# Color_music_board_with_mic.net
KiCad netlist of a schematic drawn in EAGLE
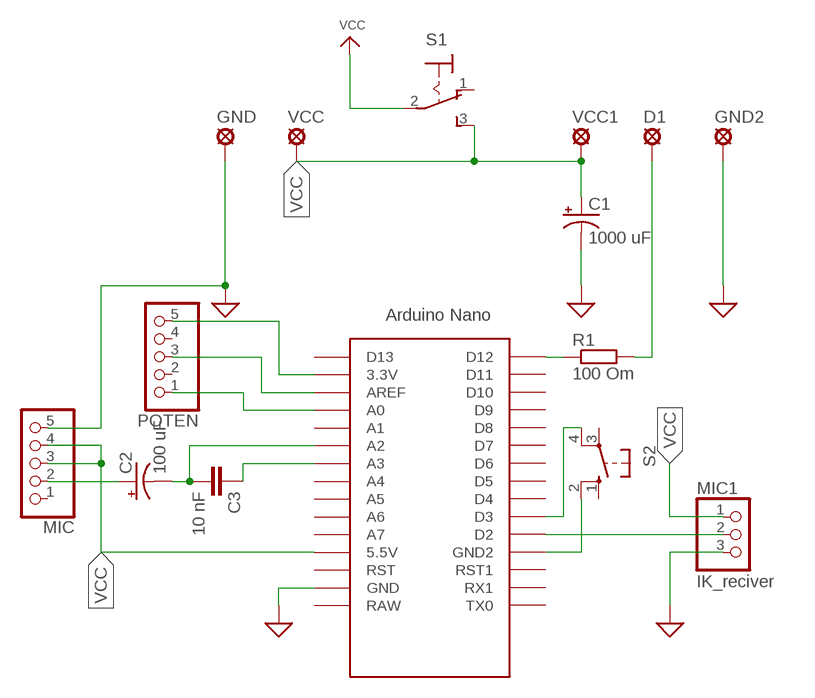
[diagram p0: schematic, sheet 1]

(export (version "E")
  (design (tool "Eeschema 10.0.6"))
  (components
    (comp (ref "C1")
      (value "1000 uF")
      (footprint "eagle-import:TT5D10")
      (libsource (lib "eagle-import") (part "CPOL-USTT5D10"))
    )
    (comp (ref "C2")
      (value "100 uF")
      (footprint "eagle-import:E2,5-6")
      (libsource (lib "eagle-import") (part "CPOL-USE2.5-6"))
    )
    (comp (ref "C3")
      (value "10 nF")
      (footprint "eagle-import:C2.5-2")
      (libsource (lib "eagle-import") (part "C2.5/2"))
    )
    (comp (ref "D1")
      (value "SE14")
      (footprint "eagle-import:SE14")
      (libsource (lib "eagle-import") (part "SE14"))
    )
    (comp (ref "GND")
      (value "SE14")
      (footprint "eagle-import:SE14")
      (libsource (lib "eagle-import") (part "SE14"))
    )
    (comp (ref "GND2")
      (value "SE14")
      (footprint "eagle-import:SE14")
      (libsource (lib "eagle-import") (part "SE14"))
    )
    (comp (ref "MIC")
      (value "PINHD-1X5")
      (footprint "eagle-import:1X05")
      (libsource (lib "eagle-import") (part "PINHD-1X5"))
    )
    (comp (ref "MIC1")
      (value "IK_reciver")
      (footprint "eagle-import:1X03")
      (libsource (lib "eagle-import") (part "PINHD-1X3"))
    )
    (comp (ref "POTEN")
      (value "PINHD-1X5")
      (footprint "eagle-import:1X05")
      (libsource (lib "eagle-import") (part "PINHD-1X5"))
    )
    (comp (ref "R1")
      (value "100 Om")
      (footprint "eagle-import:0207_7")
      (libsource (lib "eagle-import") (part "R-EU_0207/7"))
    )
    (comp (ref "S1")
      (value "320-916")
      (footprint "eagle-import:320-916")
      (libsource (lib "eagle-import") (part "320-916"))
    )
    (comp (ref "S2")
      (value "10-XX")
      (footprint "eagle-import:B3F-10XX")
      (fields (field (name "MPN") "B3F-1000"))
      (libsource (lib "eagle-import") (part "10-XX"))
    )
    (comp (ref "U$1")
      (value "NANO")
      (footprint "eagle-import:NANO")
      (libsource (lib "eagle-import") (part "NANO"))
    )
    (comp (ref "VCC")
      (value "SE14")
      (footprint "eagle-import:SE14")
      (libsource (lib "eagle-import") (part "SE14"))
    )
    (comp (ref "VCC1")
      (value "SE14")
      (footprint "eagle-import:SE14")
      (libsource (lib "eagle-import") (part "SE14"))
    )
  )
  (nets
    (net (code "1") (name "Net-(C2-Pad+)") (class "Default")
      (node (ref "C2") (pin "+") (pinfunction "+_+") (pintype "passive"))
      (node (ref "MIC") (pin "2") (pinfunction "2_2") (pintype "passive"))
    )
    (net (code "2") (name "Net-(C2-Pad-)") (class "Default")
      (node (ref "C2") (pin "-") (pinfunction "-_-") (pintype "passive"))
      (node (ref "C3") (pin "2") (pinfunction "2_2") (pintype "passive"))
      (node (ref "U$1") (pin "A2") (pinfunction "A2_A2") (pintype "bidirectional"))
    )
    (net (code "3") (name "Net-(C3-Pad1)") (class "Default")
      (node (ref "C3") (pin "1") (pinfunction "1_1") (pintype "passive"))
      (node (ref "U$1") (pin "A3") (pinfunction "A3_A3") (pintype "bidirectional"))
    )
    (net (code "4") (name "Net-(D1-PadMP)") (class "Default")
      (node (ref "D1") (pin "MP") (pinfunction "MP_MP") (pintype "passive"))
      (node (ref "R1") (pin "2") (pinfunction "2_2") (pintype "passive"))
    )
    (net (code "5") (name "Net-(MIC1-Pad2)") (class "Default")
      (node (ref "MIC1") (pin "2") (pinfunction "2_2") (pintype "passive"))
      (node (ref "U$1") (pin "D2") (pinfunction "D2_D2") (pintype "bidirectional"))
    )
    (net (code "6") (name "Net-(POTEN-Pad1)") (class "Default")
      (node (ref "POTEN") (pin "1") (pinfunction "1_1") (pintype "passive"))
      (node (ref "U$1") (pin "A0") (pinfunction "A0_A0") (pintype "bidirectional"))
    )
    (net (code "7") (name "Net-(POTEN-Pad3)") (class "Default")
      (node (ref "POTEN") (pin "3") (pinfunction "3_3") (pintype "passive"))
      (node (ref "U$1") (pin "AREF") (pinfunction "AREF_AREF") (pintype "bidirectional"))
    )
    (net (code "8") (name "Net-(POTEN-Pad5)") (class "Default")
      (node (ref "POTEN") (pin "5") (pinfunction "5_5") (pintype "passive"))
      (node (ref "U$1") (pin "3.3V") (pinfunction "3.3V_3.3V") (pintype "bidirectional"))
    )
    (net (code "9") (name "Net-(R1-Pad1)") (class "Default")
      (node (ref "R1") (pin "1") (pinfunction "1_1") (pintype "passive"))
      (node (ref "U$1") (pin "D12") (pinfunction "D12_D12") (pintype "bidirectional"))
    )
    (net (code "10") (name "Net-(S2-P1)") (class "Default")
      (node (ref "S2") (pin "4") (pinfunction "P1_4") (pintype "passive"))
      (node (ref "U$1") (pin "D3") (pinfunction "D3_D3") (pintype "bidirectional"))
    )
    (net (code "11") (name "Net-(S2-S1)") (class "Default")
      (node (ref "S2") (pin "2") (pinfunction "S1_2") (pintype "passive"))
      (node (ref "U$1") (pin "GND1") (pinfunction "GND2_GND1") (pintype "bidirectional"))
    )
    (net (code "12") (name "SUP") (class "Default")
      (node (ref "C1") (pin "-") (pinfunction "-_-") (pintype "passive"))
      (node (ref "GND") (pin "MP") (pinfunction "MP_MP") (pintype "passive"))
      (node (ref "GND2") (pin "MP") (pinfunction "MP_MP") (pintype "passive"))
      (node (ref "MIC") (pin "5") (pinfunction "5_5") (pintype "passive"))
      (node (ref "MIC1") (pin "3") (pinfunction "3_3") (pintype "passive"))
      (node (ref "U$1") (pin "GND") (pinfunction "GND_GND") (pintype "bidirectional"))
    )
    (net (code "13") (name "VCC") (class "Default")
      (node (ref "C1") (pin "+") (pinfunction "+_+") (pintype "passive"))
      (node (ref "MIC") (pin "3") (pinfunction "3_3") (pintype "passive"))
      (node (ref "MIC") (pin "4") (pinfunction "4_4") (pintype "passive"))
      (node (ref "MIC1") (pin "1") (pinfunction "1_1") (pintype "passive"))
      (node (ref "S1") (pin "2") (pinfunction "P_2") (pintype "passive"))
      (node (ref "S1") (pin "3") (pinfunction "S_3") (pintype "passive"))
      (node (ref "U$1") (pin "5V") (pinfunction "5.5V_5V") (pintype "bidirectional"))
      (node (ref "VCC") (pin "MP") (pinfunction "MP_MP") (pintype "passive"))
      (node (ref "VCC1") (pin "MP") (pinfunction "MP_MP") (pintype "passive"))
    )
    (net (code "14") (name "unconnected-(MIC-Pad1)") (class "Default")
      (node (ref "MIC") (pin "1") (pinfunction "1_1") (pintype "passive"))
    )
    (net (code "15") (name "unconnected-(POTEN-Pad2)") (class "Default")
      (node (ref "POTEN") (pin "2") (pinfunction "2_2") (pintype "passive"))
    )
    (net (code "16") (name "unconnected-(POTEN-Pad4)") (class "Default")
      (node (ref "POTEN") (pin "4") (pinfunction "4_4") (pintype "passive"))
    )
    (net (code "17") (name "unconnected-(S1-O-Pad1)") (class "Default")
      (node (ref "S1") (pin "1") (pinfunction "O_1") (pintype "passive"))
    )
    (net (code "18") (name "unconnected-(S2-P-Pad3)") (class "Default")
      (node (ref "S2") (pin "3") (pinfunction "P_3") (pintype "passive"))
    )
    (net (code "19") (name "unconnected-(S2-S-Pad1)") (class "Default")
      (node (ref "S2") (pin "1") (pinfunction "S_1") (pintype "passive"))
    )
    (net (code "20") (name "unconnected-(U$1-PadA1)") (class "Default")
      (node (ref "U$1") (pin "A1") (pinfunction "A1_A1") (pintype "bidirectional"))
    )
    (net (code "21") (name "unconnected-(U$1-PadA4)") (class "Default")
      (node (ref "U$1") (pin "A4") (pinfunction "A4_A4") (pintype "bidirectional"))
    )
    (net (code "22") (name "unconnected-(U$1-PadA5)") (class "Default")
      (node (ref "U$1") (pin "A5") (pinfunction "A5_A5") (pintype "bidirectional"))
    )
    (net (code "23") (name "unconnected-(U$1-PadA6)") (class "Default")
      (node (ref "U$1") (pin "A6") (pinfunction "A6_A6") (pintype "bidirectional"))
    )
    (net (code "24") (name "unconnected-(U$1-PadA7)") (class "Default")
      (node (ref "U$1") (pin "A7") (pinfunction "A7_A7") (pintype "bidirectional"))
    )
    (net (code "25") (name "unconnected-(U$1-PadD4)") (class "Default")
      (node (ref "U$1") (pin "D4") (pinfunction "D4_D4") (pintype "bidirectional"))
    )
    (net (code "26") (name "unconnected-(U$1-PadD5)") (class "Default")
      (node (ref "U$1") (pin "D5") (pinfunction "D5_D5") (pintype "bidirectional"))
    )
    (net (code "27") (name "unconnected-(U$1-PadD6)") (class "Default")
      (node (ref "U$1") (pin "D6") (pinfunction "D6_D6") (pintype "bidirectional"))
    )
    (net (code "28") (name "unconnected-(U$1-PadD7)") (class "Default")
      (node (ref "U$1") (pin "D7") (pinfunction "D7_D7") (pintype "bidirectional"))
    )
    (net (code "29") (name "unconnected-(U$1-PadD8)") (class "Default")
      (node (ref "U$1") (pin "D8") (pinfunction "D8_D8") (pintype "bidirectional"))
    )
    (net (code "30") (name "unconnected-(U$1-PadD9)") (class "Default")
      (node (ref "U$1") (pin "D9") (pinfunction "D9_D9") (pintype "bidirectional"))
    )
    (net (code "31") (name "unconnected-(U$1-PadD10)") (class "Default")
      (node (ref "U$1") (pin "D10") (pinfunction "D10_D10") (pintype "bidirectional"))
    )
    (net (code "32") (name "unconnected-(U$1-PadD11)") (class "Default")
      (node (ref "U$1") (pin "D11") (pinfunction "D11_D11") (pintype "bidirectional"))
    )
    (net (code "33") (name "unconnected-(U$1-PadD13)") (class "Default")
      (node (ref "U$1") (pin "D13") (pinfunction "D13_D13") (pintype "bidirectional"))
    )
    (net (code "34") (name "unconnected-(U$1-PadICSP1)") (class "Default")
      (node (ref "U$1") (pin "ICSP1") (pinfunction "ICSP1_ICSP1") (pintype "bidirectional"))
    )
    (net (code "35") (name "unconnected-(U$1-PadICSP2)") (class "Default")
      (node (ref "U$1") (pin "ICSP2") (pinfunction "ICSP2_ICSP2") (pintype "bidirectional"))
    )
    (net (code "36") (name "unconnected-(U$1-PadICSP3)") (class "Default")
      (node (ref "U$1") (pin "ICSP3") (pinfunction "ICSP3_ICSP3") (pintype "bidirectional"))
    )
    (net (code "37") (name "unconnected-(U$1-PadICSP4)") (class "Default")
      (node (ref "U$1") (pin "ICSP4") (pinfunction "ICSP4_ICSP4") (pintype "bidirectional"))
    )
    (net (code "38") (name "unconnected-(U$1-PadICSP5)") (class "Default")
      (node (ref "U$1") (pin "ICSP5") (pinfunction "ICSP5_ICSP5") (pintype "bidirectional"))
    )
    (net (code "39") (name "unconnected-(U$1-PadICSP6)") (class "Default")
      (node (ref "U$1") (pin "ICSP6") (pinfunction "ICSP6_ICSP6") (pintype "bidirectional"))
    )
    (net (code "40") (name "unconnected-(U$1-PadRAW)") (class "Default")
      (node (ref "U$1") (pin "RAW") (pinfunction "RAW_RAW") (pintype "bidirectional"))
    )
    (net (code "41") (name "unconnected-(U$1-PadRST)") (class "Default")
      (node (ref "U$1") (pin "RST") (pinfunction "RST_RST") (pintype "bidirectional"))
    )
    (net (code "42") (name "unconnected-(U$1-PadRST1)") (class "Default")
      (node (ref "U$1") (pin "RST1") (pinfunction "RST1_RST1") (pintype "bidirectional"))
    )
    (net (code "43") (name "unconnected-(U$1-PadRX1)") (class "Default")
      (node (ref "U$1") (pin "RX1") (pinfunction "RX1_RX1") (pintype "bidirectional"))
    )
    (net (code "44") (name "unconnected-(U$1-PadTX0)") (class "Default")
      (node (ref "U$1") (pin "TX0") (pinfunction "TX0_TX0") (pintype "bidirectional"))
    )
  )
)
